# ssr8ch.net
KiCad netlist of a schematic drawn in EAGLE
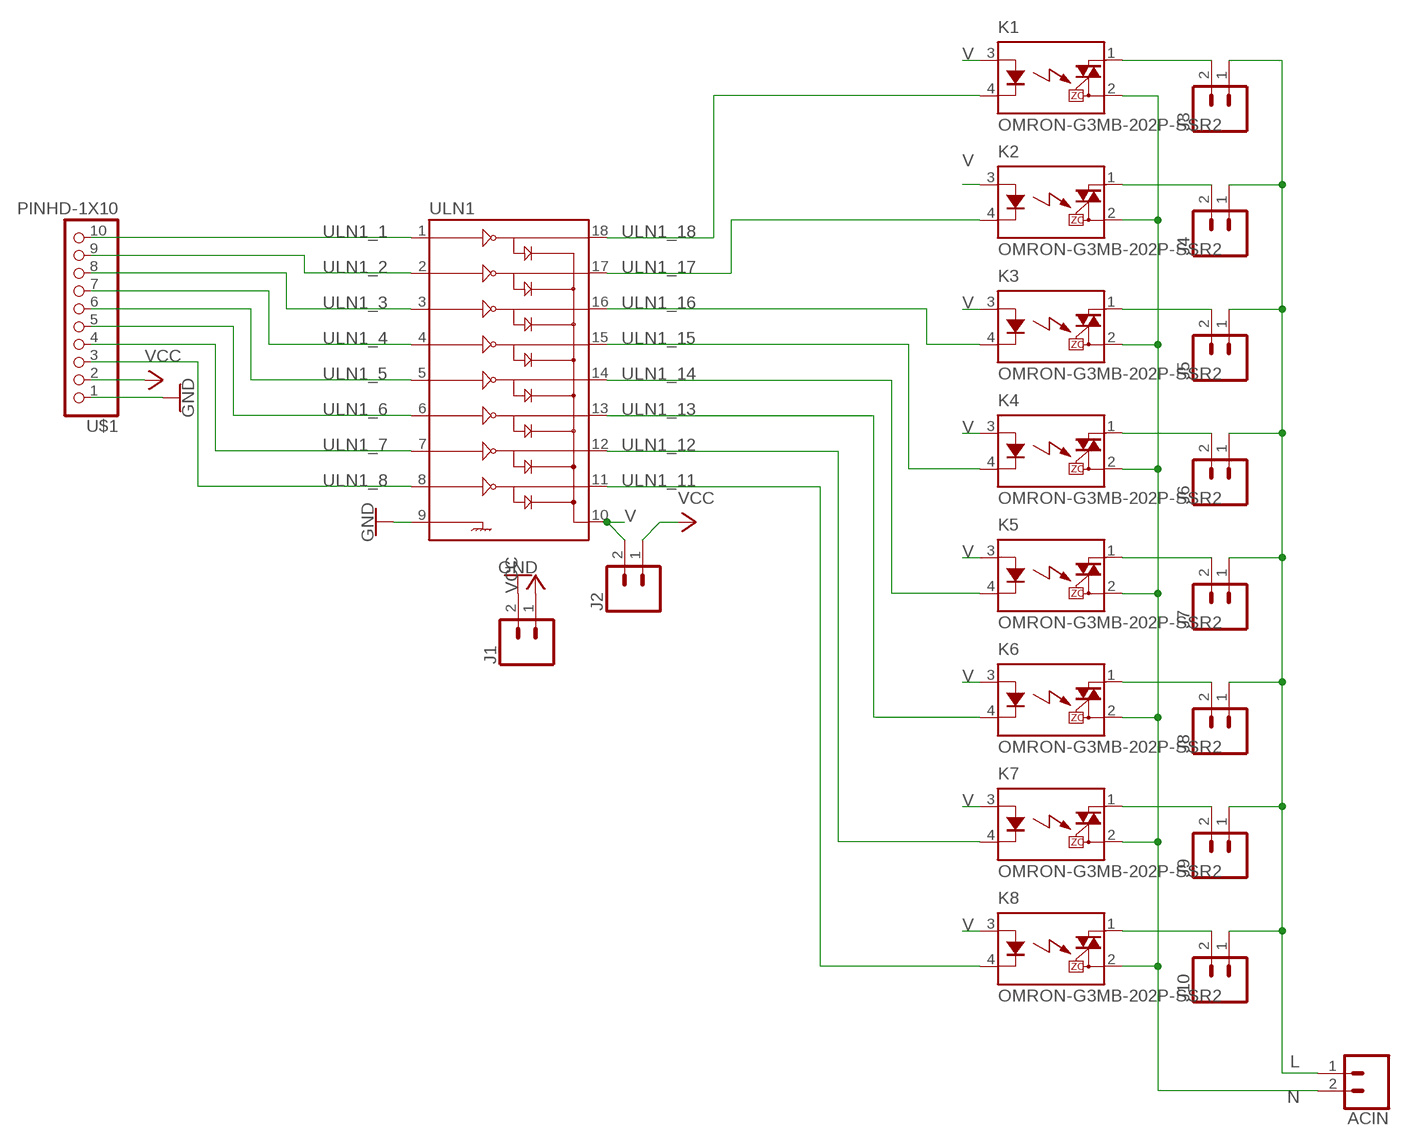
[diagram p0: schematic, sheet 1]

(export (version "E")
  (design (tool "Eeschema 10.0.6"))
  (components
    (comp (ref "ACIN")
      (value "CONN_025MM")
      (footprint "eagle-import:SCREWTERMINAL-5MM-2")
      (libsource (lib "eagle-import") (part "CONN_025MM"))
    )
    (comp (ref "J1")
      (value "CONN_025MM")
      (footprint "eagle-import:SCREWTERMINAL-5MM-2")
      (libsource (lib "eagle-import") (part "CONN_025MM"))
    )
    (comp (ref "J2")
      (value "CONN_021X02_NO_SILK")
      (footprint "eagle-import:1X02_NO_SILK")
      (libsource (lib "eagle-import") (part "CONN_021X02_NO_SILK"))
    )
    (comp (ref "J3")
      (value "CONN_025MM")
      (footprint "eagle-import:SCREWTERMINAL-5MM-2")
      (libsource (lib "eagle-import") (part "CONN_025MM"))
    )
    (comp (ref "J4")
      (value "CONN_025MM")
      (footprint "eagle-import:SCREWTERMINAL-5MM-2")
      (libsource (lib "eagle-import") (part "CONN_025MM"))
    )
    (comp (ref "J5")
      (value "CONN_025MM")
      (footprint "eagle-import:SCREWTERMINAL-5MM-2")
      (libsource (lib "eagle-import") (part "CONN_025MM"))
    )
    (comp (ref "J6")
      (value "CONN_025MM")
      (footprint "eagle-import:SCREWTERMINAL-5MM-2")
      (libsource (lib "eagle-import") (part "CONN_025MM"))
    )
    (comp (ref "J7")
      (value "CONN_025MM")
      (footprint "eagle-import:SCREWTERMINAL-5MM-2")
      (libsource (lib "eagle-import") (part "CONN_025MM"))
    )
    (comp (ref "J8")
      (value "CONN_025MM")
      (footprint "eagle-import:SCREWTERMINAL-5MM-2")
      (libsource (lib "eagle-import") (part "CONN_025MM"))
    )
    (comp (ref "J9")
      (value "CONN_025MM")
      (footprint "eagle-import:SCREWTERMINAL-5MM-2")
      (libsource (lib "eagle-import") (part "CONN_025MM"))
    )
    (comp (ref "J10")
      (value "CONN_025MM")
      (footprint "eagle-import:SCREWTERMINAL-5MM-2")
      (libsource (lib "eagle-import") (part "CONN_025MM"))
    )
    (comp (ref "K1")
      (value "OMRON-G3MB-202P-SSR2")
      (footprint "eagle-import:OMRON-G3MB-202P-SSR")
      (fields (field (name "MPN") "S202S02F"))
      (libsource (lib "eagle-import") (part "OMRON-G3MB-202P-SSR2"))
    )
    (comp (ref "K2")
      (value "OMRON-G3MB-202P-SSR2")
      (footprint "eagle-import:OMRON-G3MB-202P-SSR")
      (fields (field (name "MPN") "S202S02F"))
      (libsource (lib "eagle-import") (part "OMRON-G3MB-202P-SSR2"))
    )
    (comp (ref "K3")
      (value "OMRON-G3MB-202P-SSR2")
      (footprint "eagle-import:OMRON-G3MB-202P-SSR")
      (fields (field (name "MPN") "S202S02F"))
      (libsource (lib "eagle-import") (part "OMRON-G3MB-202P-SSR2"))
    )
    (comp (ref "K4")
      (value "OMRON-G3MB-202P-SSR2")
      (footprint "eagle-import:OMRON-G3MB-202P-SSR")
      (fields (field (name "MPN") "S202S02F"))
      (libsource (lib "eagle-import") (part "OMRON-G3MB-202P-SSR2"))
    )
    (comp (ref "K5")
      (value "OMRON-G3MB-202P-SSR2")
      (footprint "eagle-import:OMRON-G3MB-202P-SSR")
      (fields (field (name "MPN") "S202S02F"))
      (libsource (lib "eagle-import") (part "OMRON-G3MB-202P-SSR2"))
    )
    (comp (ref "K6")
      (value "OMRON-G3MB-202P-SSR2")
      (footprint "eagle-import:OMRON-G3MB-202P-SSR")
      (fields (field (name "MPN") "S202S02F"))
      (libsource (lib "eagle-import") (part "OMRON-G3MB-202P-SSR2"))
    )
    (comp (ref "K7")
      (value "OMRON-G3MB-202P-SSR2")
      (footprint "eagle-import:OMRON-G3MB-202P-SSR")
      (fields (field (name "MPN") "S202S02F"))
      (libsource (lib "eagle-import") (part "OMRON-G3MB-202P-SSR2"))
    )
    (comp (ref "K8")
      (value "OMRON-G3MB-202P-SSR2")
      (footprint "eagle-import:OMRON-G3MB-202P-SSR")
      (fields (field (name "MPN") "S202S02F"))
      (libsource (lib "eagle-import") (part "OMRON-G3MB-202P-SSR2"))
    )
    (comp (ref "U$1")
      (value "PINHD-1X10")
      (footprint "eagle-import:1X10-BIG")
      (libsource (lib "eagle-import") (part "PINHD-1X10"))
    )
    (comp (ref "ULN1")
      (value "ULN2803DIP")
      (footprint "eagle-import:DIL18")
      (libsource (lib "eagle-import") (part "ULN2803DIP"))
    )
  )
  (nets
    (net (code "1") (name "/L") (class "Default")
      (node (ref "ACIN") (pin "1") (pinfunction "1_1") (pintype "passive"))
      (node (ref "J10") (pin "1") (pinfunction "1_1") (pintype "passive"))
      (node (ref "J3") (pin "1") (pinfunction "1_1") (pintype "passive"))
      (node (ref "J4") (pin "1") (pinfunction "1_1") (pintype "passive"))
      (node (ref "J5") (pin "1") (pinfunction "1_1") (pintype "passive"))
      (node (ref "J6") (pin "1") (pinfunction "1_1") (pintype "passive"))
      (node (ref "J7") (pin "1") (pinfunction "1_1") (pintype "passive"))
      (node (ref "J8") (pin "1") (pinfunction "1_1") (pintype "passive"))
      (node (ref "J9") (pin "1") (pinfunction "1_1") (pintype "passive"))
    )
    (net (code "2") (name "/N") (class "Default")
      (node (ref "ACIN") (pin "2") (pinfunction "2_2") (pintype "passive"))
      (node (ref "K1") (pin "2") (pinfunction "DS2_2") (pintype "passive"))
      (node (ref "K2") (pin "2") (pinfunction "DS2_2") (pintype "passive"))
      (node (ref "K3") (pin "2") (pinfunction "DS2_2") (pintype "passive"))
      (node (ref "K4") (pin "2") (pinfunction "DS2_2") (pintype "passive"))
      (node (ref "K5") (pin "2") (pinfunction "DS2_2") (pintype "passive"))
      (node (ref "K6") (pin "2") (pinfunction "DS2_2") (pintype "passive"))
      (node (ref "K7") (pin "2") (pinfunction "DS2_2") (pintype "passive"))
      (node (ref "K8") (pin "2") (pinfunction "DS2_2") (pintype "passive"))
    )
    (net (code "3") (name "/ULN1_1") (class "Default")
      (node (ref "U$1") (pin "10") (pinfunction "10_10") (pintype "passive"))
      (node (ref "ULN1") (pin "1") (pinfunction "1_1") (pintype "bidirectional"))
    )
    (net (code "4") (name "/ULN1_2") (class "Default")
      (node (ref "U$1") (pin "9") (pinfunction "9_9") (pintype "passive"))
      (node (ref "ULN1") (pin "2") (pinfunction "2_2") (pintype "bidirectional"))
    )
    (net (code "5") (name "/ULN1_3") (class "Default")
      (node (ref "U$1") (pin "8") (pinfunction "8_8") (pintype "passive"))
      (node (ref "ULN1") (pin "3") (pinfunction "3_3") (pintype "bidirectional"))
    )
    (net (code "6") (name "/ULN1_4") (class "Default")
      (node (ref "U$1") (pin "7") (pinfunction "7_7") (pintype "passive"))
      (node (ref "ULN1") (pin "4") (pinfunction "4_4") (pintype "bidirectional"))
    )
    (net (code "7") (name "/ULN1_5") (class "Default")
      (node (ref "U$1") (pin "6") (pinfunction "6_6") (pintype "passive"))
      (node (ref "ULN1") (pin "5") (pinfunction "5_5") (pintype "bidirectional"))
    )
    (net (code "8") (name "/ULN1_6") (class "Default")
      (node (ref "U$1") (pin "5") (pinfunction "5_5") (pintype "passive"))
      (node (ref "ULN1") (pin "6") (pinfunction "6_6") (pintype "bidirectional"))
    )
    (net (code "9") (name "/ULN1_7") (class "Default")
      (node (ref "U$1") (pin "4") (pinfunction "4_4") (pintype "passive"))
      (node (ref "ULN1") (pin "7") (pinfunction "7_7") (pintype "bidirectional"))
    )
    (net (code "10") (name "/ULN1_8") (class "Default")
      (node (ref "U$1") (pin "3") (pinfunction "3_3") (pintype "passive"))
      (node (ref "ULN1") (pin "8") (pinfunction "8_8") (pintype "bidirectional"))
    )
    (net (code "11") (name "/ULN1_11") (class "Default")
      (node (ref "K8") (pin "4") (pinfunction "K_4") (pintype "passive"))
      (node (ref "ULN1") (pin "11") (pinfunction "11_11") (pintype "bidirectional"))
    )
    (net (code "12") (name "/ULN1_12") (class "Default")
      (node (ref "K7") (pin "4") (pinfunction "K_4") (pintype "passive"))
      (node (ref "ULN1") (pin "12") (pinfunction "12_12") (pintype "bidirectional"))
    )
    (net (code "13") (name "/ULN1_13") (class "Default")
      (node (ref "K6") (pin "4") (pinfunction "K_4") (pintype "passive"))
      (node (ref "ULN1") (pin "13") (pinfunction "13_13") (pintype "bidirectional"))
    )
    (net (code "14") (name "/ULN1_14") (class "Default")
      (node (ref "K5") (pin "4") (pinfunction "K_4") (pintype "passive"))
      (node (ref "ULN1") (pin "14") (pinfunction "14_14") (pintype "bidirectional"))
    )
    (net (code "15") (name "/ULN1_15") (class "Default")
      (node (ref "K4") (pin "4") (pinfunction "K_4") (pintype "passive"))
      (node (ref "ULN1") (pin "15") (pinfunction "15_15") (pintype "bidirectional"))
    )
    (net (code "16") (name "/ULN1_16") (class "Default")
      (node (ref "K3") (pin "4") (pinfunction "K_4") (pintype "passive"))
      (node (ref "ULN1") (pin "16") (pinfunction "16_16") (pintype "bidirectional"))
    )
    (net (code "17") (name "/ULN1_17") (class "Default")
      (node (ref "K2") (pin "4") (pinfunction "K_4") (pintype "passive"))
      (node (ref "ULN1") (pin "17") (pinfunction "17_17") (pintype "bidirectional"))
    )
    (net (code "18") (name "/ULN1_18") (class "Default")
      (node (ref "K1") (pin "4") (pinfunction "K_4") (pintype "passive"))
      (node (ref "ULN1") (pin "18") (pinfunction "18_18") (pintype "bidirectional"))
    )
    (net (code "19") (name "/V") (class "Default")
      (node (ref "J2") (pin "2") (pinfunction "2_2") (pintype "passive"))
      (node (ref "K1") (pin "3") (pinfunction "A_3") (pintype "passive"))
      (node (ref "K2") (pin "3") (pinfunction "A_3") (pintype "passive"))
      (node (ref "K3") (pin "3") (pinfunction "A_3") (pintype "passive"))
      (node (ref "K4") (pin "3") (pinfunction "A_3") (pintype "passive"))
      (node (ref "K5") (pin "3") (pinfunction "A_3") (pintype "passive"))
      (node (ref "K6") (pin "3") (pinfunction "A_3") (pintype "passive"))
      (node (ref "K7") (pin "3") (pinfunction "A_3") (pintype "passive"))
      (node (ref "K8") (pin "3") (pinfunction "A_3") (pintype "passive"))
      (node (ref "ULN1") (pin "10") (pinfunction "10_10") (pintype "bidirectional"))
    )
    (net (code "20") (name "GND") (class "Default")
      (node (ref "J1") (pin "2") (pinfunction "2_2") (pintype "passive"))
      (node (ref "U$1") (pin "1") (pinfunction "1_1") (pintype "passive"))
      (node (ref "ULN1") (pin "9") (pinfunction "9_9") (pintype "bidirectional"))
    )
    (net (code "21") (name "Net-(K1-DS1)") (class "Default")
      (node (ref "J3") (pin "2") (pinfunction "2_2") (pintype "passive"))
      (node (ref "K1") (pin "1") (pinfunction "DS1_1") (pintype "passive"))
    )
    (net (code "22") (name "Net-(K2-DS1)") (class "Default")
      (node (ref "J4") (pin "2") (pinfunction "2_2") (pintype "passive"))
      (node (ref "K2") (pin "1") (pinfunction "DS1_1") (pintype "passive"))
    )
    (net (code "23") (name "Net-(K3-DS1)") (class "Default")
      (node (ref "J5") (pin "2") (pinfunction "2_2") (pintype "passive"))
      (node (ref "K3") (pin "1") (pinfunction "DS1_1") (pintype "passive"))
    )
    (net (code "24") (name "Net-(K4-DS1)") (class "Default")
      (node (ref "J6") (pin "2") (pinfunction "2_2") (pintype "passive"))
      (node (ref "K4") (pin "1") (pinfunction "DS1_1") (pintype "passive"))
    )
    (net (code "25") (name "Net-(K5-DS1)") (class "Default")
      (node (ref "J7") (pin "2") (pinfunction "2_2") (pintype "passive"))
      (node (ref "K5") (pin "1") (pinfunction "DS1_1") (pintype "passive"))
    )
    (net (code "26") (name "Net-(K6-DS1)") (class "Default")
      (node (ref "J8") (pin "2") (pinfunction "2_2") (pintype "passive"))
      (node (ref "K6") (pin "1") (pinfunction "DS1_1") (pintype "passive"))
    )
    (net (code "27") (name "Net-(K7-DS1)") (class "Default")
      (node (ref "J9") (pin "2") (pinfunction "2_2") (pintype "passive"))
      (node (ref "K7") (pin "1") (pinfunction "DS1_1") (pintype "passive"))
    )
    (net (code "28") (name "Net-(K8-DS1)") (class "Default")
      (node (ref "J10") (pin "2") (pinfunction "2_2") (pintype "passive"))
      (node (ref "K8") (pin "1") (pinfunction "DS1_1") (pintype "passive"))
    )
    (net (code "29") (name "VCC") (class "Default")
      (node (ref "J1") (pin "1") (pinfunction "1_1") (pintype "passive"))
      (node (ref "J2") (pin "1") (pinfunction "1_1") (pintype "passive"))
      (node (ref "U$1") (pin "2") (pinfunction "2_2") (pintype "passive"))
    )
  )
)
